# SMPSv2.net
KiCad netlist of a schematic drawn in EAGLE
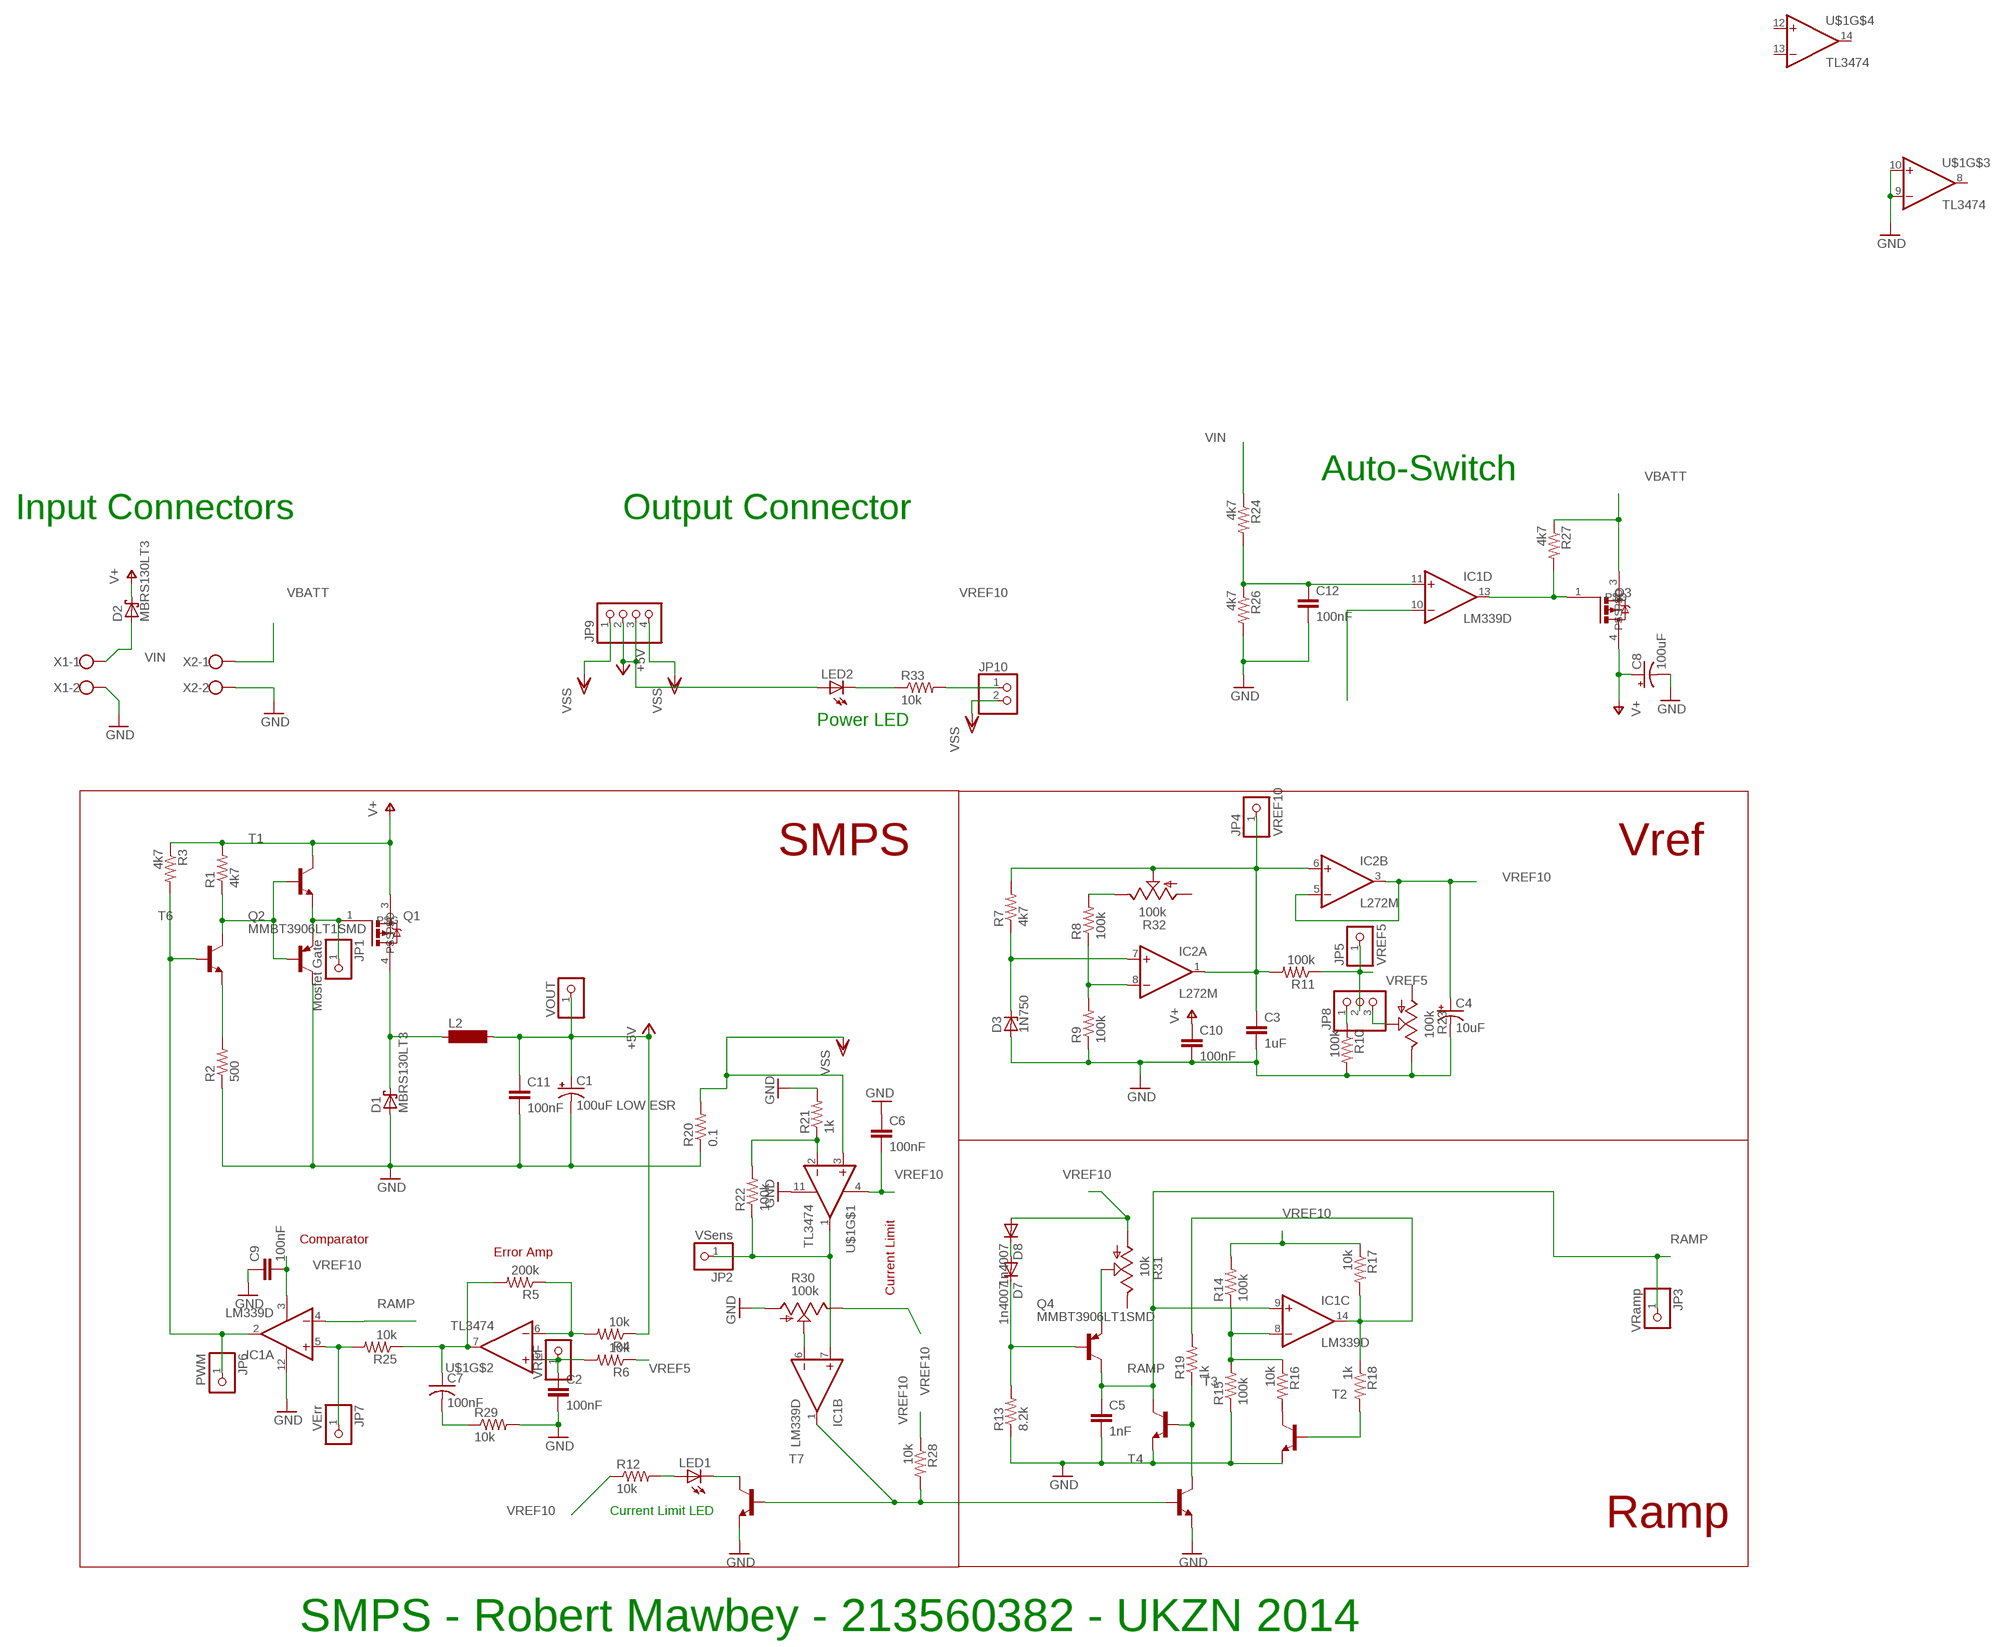
[diagram p0: schematic, sheet 1]

(export (version "E")
  (design (tool "Eeschema 10.0.6"))
  (components
    (comp (ref "C1")
      (value "100uF LOW ESR")
      (footprint "eagle-import:PANASONIC_D")
      (libsource (lib "eagle-import") (part "CPOL-USD"))
    )
    (comp (ref "C2")
      (value "100nF")
      (footprint "eagle-import:C0805")
      (libsource (lib "eagle-import") (part "C-EUC0805"))
    )
    (comp (ref "C3")
      (value "1uF")
      (footprint "eagle-import:C0805")
      (libsource (lib "eagle-import") (part "C-EUC0805"))
    )
    (comp (ref "C4")
      (value "10uF")
      (footprint "eagle-import:E5-10,5")
      (libsource (lib "eagle-import") (part "CPOL-USE5-10.5"))
    )
    (comp (ref "C5")
      (value "1nF")
      (footprint "eagle-import:C0805")
      (libsource (lib "eagle-import") (part "C-EUC0805"))
    )
    (comp (ref "C6")
      (value "100nF")
      (footprint "eagle-import:C0805")
      (libsource (lib "eagle-import") (part "C-EUC0805"))
    )
    (comp (ref "C7")
      (value "100nF")
      (footprint "eagle-import:C0805")
      (libsource (lib "eagle-import") (part "C-USC0805"))
    )
    (comp (ref "C8")
      (value "100uF")
      (footprint "eagle-import:E5-13")
      (libsource (lib "eagle-import") (part "CPOL-USE5-13"))
    )
    (comp (ref "C9")
      (value "100nF")
      (footprint "eagle-import:C0805")
      (libsource (lib "eagle-import") (part "C-EUC0805"))
    )
    (comp (ref "C10")
      (value "100nF")
      (footprint "eagle-import:C0805")
      (libsource (lib "eagle-import") (part "C-EUC0805"))
    )
    (comp (ref "C11")
      (value "100nF")
      (footprint "eagle-import:C0805")
      (libsource (lib "eagle-import") (part "C-EUC0805"))
    )
    (comp (ref "C12")
      (value "100nF")
      (footprint "eagle-import:C0805")
      (libsource (lib "eagle-import") (part "C-EUC0805"))
    )
    (comp (ref "D1")
      (value "MBRS130LT3")
      (footprint "eagle-import:SMB")
      (libsource (lib "eagle-import") (part "MBRS130LT3"))
    )
    (comp (ref "D2")
      (value "MBRS130LT3")
      (footprint "eagle-import:SMB")
      (libsource (lib "eagle-import") (part "MBRS130LT3"))
    )
    (comp (ref "D3")
      (value "1N750")
      (footprint "eagle-import:ZDIO-7.5")
      (libsource (lib "eagle-import") (part "ZENER-DIODEZD-7.5"))
    )
    (comp (ref "D7")
      (value "1n4007")
      (footprint "eagle-import:DO-214AC")
      (libsource (lib "eagle-import") (part "DIODE-DO-214AC"))
    )
    (comp (ref "D8")
      (value "1n4007")
      (footprint "eagle-import:DO-214AC")
      (libsource (lib "eagle-import") (part "DIODE-DO-214AC"))
    )
    (comp (ref "IC1")
      (value "LM339D")
      (footprint "eagle-import:SO14")
      (libsource (lib "eagle-import") (part "LM339D"))
    )
    (comp (ref "IC2")
      (value "L272M")
      (footprint "eagle-import:DIL08")
      (libsource (lib "eagle-import") (part "L272M"))
    )
    (comp (ref "JP1")
      (value "Mosfet Gate")
      (footprint "eagle-import:1X01")
      (libsource (lib "eagle-import") (part "PINHD-1X1"))
    )
    (comp (ref "JP2")
      (value "VSens")
      (footprint "eagle-import:1X01")
      (libsource (lib "eagle-import") (part "PINHD-1X1"))
    )
    (comp (ref "JP3")
      (value "VRamp")
      (footprint "eagle-import:1X01")
      (libsource (lib "eagle-import") (part "PINHD-1X1"))
    )
    (comp (ref "JP4")
      (value "VREF10")
      (footprint "eagle-import:1X01")
      (libsource (lib "eagle-import") (part "PINHD-1X1"))
    )
    (comp (ref "JP5")
      (value "VREF5")
      (footprint "eagle-import:1X01")
      (libsource (lib "eagle-import") (part "PINHD-1X1"))
    )
    (comp (ref "JP6")
      (value "PWM")
      (footprint "eagle-import:1X01")
      (libsource (lib "eagle-import") (part "PINHD-1X1"))
    )
    (comp (ref "JP7")
      (value "VErr")
      (footprint "eagle-import:1X01")
      (libsource (lib "eagle-import") (part "PINHD-1X1"))
    )
    (comp (ref "JP8")
      (value "PINHD-1X3")
      (footprint "eagle-import:1X03")
      (libsource (lib "eagle-import") (part "PINHD-1X3"))
    )
    (comp (ref "JP9")
      (value "PINHD-1X4")
      (footprint "eagle-import:1X04")
      (libsource (lib "eagle-import") (part "PINHD-1X4"))
    )
    (comp (ref "JP10")
      (value "PINHD-1X2")
      (footprint "eagle-import:1X02")
      (libsource (lib "eagle-import") (part "PINHD-1X2"))
    )
    (comp (ref "L2")
      (value "BS11")
      (footprint "eagle-import:BS11")
      (libsource (lib "eagle-import") (part "BS11"))
    )
    (comp (ref "LED1")
      (value "LEDCHIPLED_0805")
      (footprint "eagle-import:CHIPLED_0805")
      (libsource (lib "eagle-import") (part "LEDCHIPLED_0805"))
    )
    (comp (ref "LED2")
      (value "LEDCHIPLED_0805")
      (footprint "eagle-import:CHIPLED_0805")
      (libsource (lib "eagle-import") (part "LEDCHIPLED_0805"))
    )
    (comp (ref "Q1")
      (value "IRFR9024NDPAK")
      (footprint "eagle-import:D-PAK_TO252AA")
      (libsource (lib "eagle-import") (part "IRFR9024NDPAK"))
    )
    (comp (ref "Q2")
      (value "MMBT3906LT1SMD")
      (footprint "eagle-import:SOT23-BEC")
      (libsource (lib "eagle-import") (part "MMBT3906SMDLT1"))
    )
    (comp (ref "Q3")
      (value "IRFR9024NDPAK")
      (footprint "eagle-import:D-PAK_TO252AA")
      (libsource (lib "eagle-import") (part "IRFR9024NDPAK"))
    )
    (comp (ref "Q4")
      (value "MMBT3906LT1SMD")
      (footprint "eagle-import:SOT23-BEC")
      (libsource (lib "eagle-import") (part "MMBT3906SMDLT1"))
    )
    (comp (ref "R1")
      (value "4k7")
      (footprint "eagle-import:R0805")
      (libsource (lib "eagle-import") (part "R-US_R0805"))
    )
    (comp (ref "R2")
      (value "500")
      (footprint "eagle-import:R0805")
      (libsource (lib "eagle-import") (part "R-US_R0805"))
    )
    (comp (ref "R3")
      (value "4k7")
      (footprint "eagle-import:R0805")
      (libsource (lib "eagle-import") (part "R-US_R0805"))
    )
    (comp (ref "R4")
      (value "10k")
      (footprint "eagle-import:R0805")
      (libsource (lib "eagle-import") (part "R-US_R0805"))
    )
    (comp (ref "R5")
      (value "200k")
      (footprint "eagle-import:R0805")
      (libsource (lib "eagle-import") (part "R-US_R0805"))
    )
    (comp (ref "R6")
      (value "10k")
      (footprint "eagle-import:R0805")
      (libsource (lib "eagle-import") (part "R-US_R0805"))
    )
    (comp (ref "R7")
      (value "4k7")
      (footprint "eagle-import:R0805")
      (libsource (lib "eagle-import") (part "R-US_R0805"))
    )
    (comp (ref "R8")
      (value "100k")
      (footprint "eagle-import:R0805")
      (libsource (lib "eagle-import") (part "R-US_R0805"))
    )
    (comp (ref "R9")
      (value "100k")
      (footprint "eagle-import:R0805")
      (libsource (lib "eagle-import") (part "R-US_R0805"))
    )
    (comp (ref "R10")
      (value "100k")
      (footprint "eagle-import:R0805")
      (libsource (lib "eagle-import") (part "R-US_R0805"))
    )
    (comp (ref "R11")
      (value "100k")
      (footprint "eagle-import:R0805")
      (libsource (lib "eagle-import") (part "R-US_R0805"))
    )
    (comp (ref "R12")
      (value "10k")
      (footprint "eagle-import:R0805")
      (libsource (lib "eagle-import") (part "R-US_R0805"))
    )
    (comp (ref "R13")
      (value "8.2k")
      (footprint "eagle-import:R0805")
      (libsource (lib "eagle-import") (part "R-US_R0805"))
    )
    (comp (ref "R14")
      (value "100k")
      (footprint "eagle-import:R0805")
      (libsource (lib "eagle-import") (part "R-US_R0805"))
    )
    (comp (ref "R15")
      (value "100k")
      (footprint "eagle-import:R0805")
      (libsource (lib "eagle-import") (part "R-US_R0805"))
    )
    (comp (ref "R16")
      (value "10k")
      (footprint "eagle-import:R0805")
      (libsource (lib "eagle-import") (part "R-US_R0805"))
    )
    (comp (ref "R17")
      (value "10k")
      (footprint "eagle-import:R0805")
      (libsource (lib "eagle-import") (part "R-US_R0805"))
    )
    (comp (ref "R18")
      (value "1k")
      (footprint "eagle-import:R0805")
      (libsource (lib "eagle-import") (part "R-US_R0805"))
    )
    (comp (ref "R19")
      (value "1k")
      (footprint "eagle-import:R0805")
      (libsource (lib "eagle-import") (part "R-US_R0805"))
    )
    (comp (ref "R20")
      (value "0.1")
      (footprint "eagle-import:R1206")
      (libsource (lib "eagle-import") (part "R-US_R1206"))
    )
    (comp (ref "R21")
      (value "1k")
      (footprint "eagle-import:R0805")
      (libsource (lib "eagle-import") (part "R-US_R0805"))
    )
    (comp (ref "R22")
      (value "100k")
      (footprint "eagle-import:R0805")
      (libsource (lib "eagle-import") (part "R-US_R0805"))
    )
    (comp (ref "R23")
      (value "100k")
      (footprint "eagle-import:B25P")
      (libsource (lib "eagle-import") (part "TRIM_US-B25P"))
    )
    (comp (ref "R24")
      (value "4k7")
      (footprint "eagle-import:R0805")
      (libsource (lib "eagle-import") (part "R-US_R0805"))
    )
    (comp (ref "R25")
      (value "10k")
      (footprint "eagle-import:R0805")
      (libsource (lib "eagle-import") (part "R-US_R0805"))
    )
    (comp (ref "R26")
      (value "4k7")
      (footprint "eagle-import:R0805")
      (libsource (lib "eagle-import") (part "R-US_R0805"))
    )
    (comp (ref "R27")
      (value "4k7")
      (footprint "eagle-import:R0805")
      (libsource (lib "eagle-import") (part "R-US_R0805"))
    )
    (comp (ref "R28")
      (value "10k")
      (footprint "eagle-import:R0805")
      (libsource (lib "eagle-import") (part "R-US_R0805"))
    )
    (comp (ref "R29")
      (value "10k")
      (footprint "eagle-import:R0805")
      (libsource (lib "eagle-import") (part "R-US_R0805"))
    )
    (comp (ref "R30")
      (value "100k")
      (footprint "eagle-import:B25P")
      (libsource (lib "eagle-import") (part "TRIM_US-B25P"))
    )
    (comp (ref "R31")
      (value "10k")
      (footprint "eagle-import:B25P")
      (libsource (lib "eagle-import") (part "TRIM_US-B25P"))
    )
    (comp (ref "R32")
      (value "100k")
      (footprint "eagle-import:B25P")
      (libsource (lib "eagle-import") (part "TRIM_US-B25P"))
    )
    (comp (ref "R33")
      (value "10k")
      (footprint "eagle-import:R0805")
      (libsource (lib "eagle-import") (part "R-US_R0805"))
    )
    (comp (ref "T1")
      (value "MMBT2222ALT1-NPN-SOT23-BEC")
      (footprint "eagle-import:SOT23-BEC")
      (libsource (lib "eagle-import") (part "-NPN-SOT23-BECMMBT2222ALT1"))
    )
    (comp (ref "T2")
      (value "MMBT2222ALT1-NPN-SOT23-BEC")
      (footprint "eagle-import:SOT23-BEC")
      (libsource (lib "eagle-import") (part "-NPN-SOT23-BECMMBT2222ALT1"))
    )
    (comp (ref "T3")
      (value "MMBT2222ALT1-NPN-SOT23-BEC")
      (footprint "eagle-import:SOT23-BEC")
      (libsource (lib "eagle-import") (part "-NPN-SOT23-BECMMBT2222ALT1"))
    )
    (comp (ref "T4")
      (value "MMBT2222ALT1-NPN-SOT23-BEC")
      (footprint "eagle-import:SOT23-BEC")
      (libsource (lib "eagle-import") (part "-NPN-SOT23-BECMMBT2222ALT1"))
    )
    (comp (ref "T6")
      (value "MMBT2222ALT1-NPN-SOT23-BEC")
      (footprint "eagle-import:SOT23-BEC")
      (libsource (lib "eagle-import") (part "-NPN-SOT23-BECMMBT2222ALT1"))
    )
    (comp (ref "T7")
      (value "MMBT2222ALT1-NPN-SOT23-BEC")
      (footprint "eagle-import:SOT23-BEC")
      (libsource (lib "eagle-import") (part "-NPN-SOT23-BECMMBT2222ALT1"))
    )
    (comp (ref "U$1")
      (value "TL3474")
      (footprint "eagle-import:SO14")
      (libsource (lib "eagle-import") (part "TL3474"))
    )
    (comp (ref "VOUT")
      (value "PINHD-1X1")
      (footprint "eagle-import:1X01")
      (libsource (lib "eagle-import") (part "PINHD-1X1"))
    )
    (comp (ref "VREF")
      (value "PINHD-1X1")
      (footprint "eagle-import:1X01")
      (libsource (lib "eagle-import") (part "PINHD-1X1"))
    )
    (comp (ref "X1")
      (value "W237-102")
      (footprint "eagle-import:W237-102")
      (fields (field (name "MPN") "237-102"))
      (libsource (lib "eagle-import") (part "W237-102"))
    )
    (comp (ref "X2")
      (value "W237-102")
      (footprint "eagle-import:W237-102")
      (fields
        (field (name "MPN") "237-102")
        (field (name "MPN_1") "237-102")
        (field (name "OC_FARNELL") "unknown")
        (field (name "OC_NEWARK") "70K9898")
      )
      (libsource (lib "eagle-import") (part "W237-102"))
    )
  )
  (nets
    (net (code "1") (name "+5V") (class "Default")
      (node (ref "C1") (pin "+") (pinfunction "+_+") (pintype "passive"))
      (node (ref "C11") (pin "1") (pinfunction "1_1") (pintype "passive"))
      (node (ref "JP9") (pin "2") (pinfunction "2_2") (pintype "passive"))
      (node (ref "JP9") (pin "3") (pinfunction "3_3") (pintype "passive"))
      (node (ref "L2") (pin "2") (pinfunction "2_2") (pintype "passive"))
      (node (ref "LED2") (pin "A") (pinfunction "A_A") (pintype "passive"))
      (node (ref "R4") (pin "1") (pinfunction "1_1") (pintype "passive"))
      (node (ref "VOUT") (pin "1") (pinfunction "1_1") (pintype "passive"))
    )
    (net (code "2") (name "/RAMP") (class "Default")
      (node (ref "C5") (pin "1") (pinfunction "1_1") (pintype "passive"))
      (node (ref "IC1") (pin "4") (pinfunction "-IN_4") (pintype "input"))
      (node (ref "IC1") (pin "9") (pinfunction "+IN_9") (pintype "input"))
      (node (ref "JP3") (pin "1") (pinfunction "1_1") (pintype "passive"))
      (node (ref "Q4") (pin "C") (pinfunction "C_C") (pintype "passive"))
      (node (ref "T3") (pin "C") (pinfunction "C_C") (pintype "passive"))
    )
    (net (code "3") (name "/VBATT") (class "Default")
      (node (ref "Q3") (pin "3") (pinfunction "P$S_3") (pintype "bidirectional"))
      (node (ref "R27") (pin "1") (pinfunction "1_1") (pintype "passive"))
      (node (ref "X2") (pin "1") (pinfunction "KL_1") (pintype "passive"))
    )
    (net (code "4") (name "/VIN") (class "Default")
      (node (ref "D2") (pin "A") (pinfunction "A_A") (pintype "passive"))
      (node (ref "R24") (pin "1") (pinfunction "1_1") (pintype "passive"))
      (node (ref "X1") (pin "1") (pinfunction "KL_1") (pintype "passive"))
    )
    (net (code "5") (name "/VREF5") (class "Default")
      (node (ref "JP5") (pin "1") (pinfunction "1_1") (pintype "passive"))
      (node (ref "JP8") (pin "2") (pinfunction "2_2") (pintype "passive"))
      (node (ref "R11") (pin "1") (pinfunction "1_1") (pintype "passive"))
      (node (ref "R6") (pin "1") (pinfunction "1_1") (pintype "passive"))
    )
    (net (code "6") (name "/VREF10") (class "Default")
      (node (ref "C4") (pin "+") (pinfunction "+_+") (pintype "passive"))
      (node (ref "C6") (pin "2") (pinfunction "2_2") (pintype "passive"))
      (node (ref "C9") (pin "2") (pinfunction "2_2") (pintype "passive"))
      (node (ref "D8") (pin "A") (pinfunction "A_A") (pintype "passive"))
      (node (ref "IC1") (pin "10") (pinfunction "-IN_10") (pintype "input"))
      (node (ref "IC1") (pin "3") (pinfunction "V+_3") (pintype "power_in"))
      (node (ref "IC2") (pin "3") (pinfunction "OUT_3") (pintype "output"))
      (node (ref "IC2") (pin "5") (pinfunction "-IN_5") (pintype "input"))
      (node (ref "R12") (pin "1") (pinfunction "1_1") (pintype "passive"))
      (node (ref "R14") (pin "2") (pinfunction "2_2") (pintype "passive"))
      (node (ref "R17") (pin "1") (pinfunction "1_1") (pintype "passive"))
      (node (ref "R28") (pin "1") (pinfunction "1_1") (pintype "passive"))
      (node (ref "R30") (pin "E") (pinfunction "E_E") (pintype "passive"))
      (node (ref "R31") (pin "A") (pinfunction "A_A") (pintype "passive"))
      (node (ref "U$1") (pin "4") (pinfunction "V+_4") (pintype "power_in"))
    )
    (net (code "7") (name "GND") (class "Default")
      (node (ref "C1") (pin "-") (pinfunction "-_-") (pintype "passive"))
      (node (ref "C10") (pin "2") (pinfunction "2_2") (pintype "passive"))
      (node (ref "C11") (pin "2") (pinfunction "2_2") (pintype "passive"))
      (node (ref "C12") (pin "2") (pinfunction "2_2") (pintype "passive"))
      (node (ref "C2") (pin "2") (pinfunction "2_2") (pintype "passive"))
      (node (ref "C3") (pin "2") (pinfunction "2_2") (pintype "passive"))
      (node (ref "C4") (pin "-") (pinfunction "-_-") (pintype "passive"))
      (node (ref "C5") (pin "2") (pinfunction "2_2") (pintype "passive"))
      (node (ref "C6") (pin "1") (pinfunction "1_1") (pintype "passive"))
      (node (ref "C8") (pin "-") (pinfunction "-_-") (pintype "passive"))
      (node (ref "C9") (pin "1") (pinfunction "1_1") (pintype "passive"))
      (node (ref "D1") (pin "A") (pinfunction "A_A") (pintype "passive"))
      (node (ref "D3") (pin "A") (pinfunction "A_A") (pintype "passive"))
      (node (ref "IC1") (pin "12") (pinfunction "GND_12") (pintype "power_in"))
      (node (ref "Q2") (pin "C") (pinfunction "C_C") (pintype "passive"))
      (node (ref "R10") (pin "2") (pinfunction "2_2") (pintype "passive"))
      (node (ref "R13") (pin "1") (pinfunction "1_1") (pintype "passive"))
      (node (ref "R15") (pin "1") (pinfunction "1_1") (pintype "passive"))
      (node (ref "R2") (pin "1") (pinfunction "1_1") (pintype "passive"))
      (node (ref "R20") (pin "1") (pinfunction "1_1") (pintype "passive"))
      (node (ref "R21") (pin "2") (pinfunction "2_2") (pintype "passive"))
      (node (ref "R23") (pin "E") (pinfunction "E_E") (pintype "passive"))
      (node (ref "R26") (pin "2") (pinfunction "2_2") (pintype "passive"))
      (node (ref "R29") (pin "2") (pinfunction "2_2") (pintype "passive"))
      (node (ref "R30") (pin "A") (pinfunction "A_A") (pintype "passive"))
      (node (ref "R9") (pin "1") (pinfunction "1_1") (pintype "passive"))
      (node (ref "T2") (pin "E") (pinfunction "E_E") (pintype "passive"))
      (node (ref "T3") (pin "E") (pinfunction "E_E") (pintype "passive"))
      (node (ref "T4") (pin "E") (pinfunction "E_E") (pintype "passive"))
      (node (ref "T7") (pin "E") (pinfunction "E_E") (pintype "passive"))
      (node (ref "U$1") (pin "10") (pinfunction "+IN_10") (pintype "input"))
      (node (ref "U$1") (pin "11") (pinfunction "V-_11") (pintype "power_in"))
      (node (ref "U$1") (pin "9") (pinfunction "-IN_9") (pintype "input"))
      (node (ref "X1") (pin "2") (pinfunction "KL_2") (pintype "passive"))
      (node (ref "X2") (pin "2") (pinfunction "KL_2") (pintype "passive"))
    )
    (net (code "8") (name "Net-(C7-Pad2)") (class "Default")
      (node (ref "C7") (pin "2") (pinfunction "2_2") (pintype "passive"))
      (node (ref "R29") (pin "1") (pinfunction "1_1") (pintype "passive"))
    )
    (net (code "9") (name "Net-(D7-PadA)") (class "Default")
      (node (ref "D7") (pin "A") (pinfunction "A_A") (pintype "passive"))
      (node (ref "D8") (pin "C") (pinfunction "C_C") (pintype "passive"))
    )
    (net (code "10") (name "Net-(D7-PadC)") (class "Default")
      (node (ref "D7") (pin "C") (pinfunction "C_C") (pintype "passive"))
      (node (ref "Q4") (pin "B") (pinfunction "B_B") (pintype "passive"))
      (node (ref "R13") (pin "2") (pinfunction "2_2") (pintype "passive"))
    )
    (net (code "11") (name "Net-(IC1A-+IN)") (class "Default")
      (node (ref "IC1") (pin "5") (pinfunction "+IN_5") (pintype "input"))
      (node (ref "JP7") (pin "1") (pinfunction "1_1") (pintype "passive"))
      (node (ref "R25") (pin "2") (pinfunction "2_2") (pintype "passive"))
    )
    (net (code "12") (name "Net-(IC1A-OUT)") (class "Default")
      (node (ref "IC1") (pin "2") (pinfunction "OUT_2") (pintype "open_collector"))
      (node (ref "JP6") (pin "1") (pinfunction "1_1") (pintype "passive"))
      (node (ref "R3") (pin "2") (pinfunction "2_2") (pintype "passive"))
      (node (ref "T6") (pin "B") (pinfunction "B_B") (pintype "passive"))
    )
    (net (code "13") (name "Net-(IC1B-+IN)") (class "Default")
      (node (ref "IC1") (pin "7") (pinfunction "+IN_7") (pintype "input"))
      (node (ref "JP2") (pin "1") (pinfunction "1_1") (pintype "passive"))
      (node (ref "R22") (pin "1") (pinfunction "1_1") (pintype "passive"))
      (node (ref "U$1") (pin "1") (pinfunction "OUT_1") (pintype "output"))
    )
    (net (code "14") (name "Net-(IC1B--IN)") (class "Default")
      (node (ref "IC1") (pin "6") (pinfunction "-IN_6") (pintype "input"))
      (node (ref "R30") (pin "S") (pinfunction "S_S") (pintype "passive"))
    )
    (net (code "15") (name "Net-(IC1B-OUT)") (class "Default")
      (node (ref "IC1") (pin "1") (pinfunction "OUT_1") (pintype "open_collector"))
      (node (ref "R28") (pin "2") (pinfunction "2_2") (pintype "passive"))
      (node (ref "T4") (pin "B") (pinfunction "B_B") (pintype "passive"))
      (node (ref "T7") (pin "B") (pinfunction "B_B") (pintype "passive"))
    )
    (net (code "16") (name "Net-(IC1C--IN)") (class "Default")
      (node (ref "IC1") (pin "8") (pinfunction "-IN_8") (pintype "input"))
      (node (ref "R14") (pin "1") (pinfunction "1_1") (pintype "passive"))
      (node (ref "R15") (pin "2") (pinfunction "2_2") (pintype "passive"))
      (node (ref "R16") (pin "1") (pinfunction "1_1") (pintype "passive"))
    )
    (net (code "17") (name "Net-(IC1C-OUT)") (class "Default")
      (node (ref "IC1") (pin "14") (pinfunction "OUT_14") (pintype "open_collector"))
      (node (ref "R17") (pin "2") (pinfunction "2_2") (pintype "passive"))
      (node (ref "R18") (pin "1") (pinfunction "1_1") (pintype "passive"))
      (node (ref "R19") (pin "2") (pinfunction "2_2") (pintype "passive"))
    )
    (net (code "18") (name "Net-(IC1D-+IN)") (class "Default")
      (node (ref "C12") (pin "1") (pinfunction "1_1") (pintype "passive"))
      (node (ref "IC1") (pin "11") (pinfunction "+IN_11") (pintype "input"))
      (node (ref "R24") (pin "2") (pinfunction "2_2") (pintype "passive"))
      (node (ref "R26") (pin "1") (pinfunction "1_1") (pintype "passive"))
    )
    (net (code "19") (name "Net-(IC1D-OUT)") (class "Default")
      (node (ref "IC1") (pin "13") (pinfunction "OUT_13") (pintype "open_collector"))
      (node (ref "Q3") (pin "1") (pinfunction "P$G_1") (pintype "bidirectional"))
      (node (ref "R27") (pin "2") (pinfunction "2_2") (pintype "passive"))
    )
    (net (code "20") (name "Net-(IC2A-+IN)") (class "Default")
      (node (ref "D3") (pin "C") (pinfunction "C_C") (pintype "passive"))
      (node (ref "IC2") (pin "7") (pinfunction "+IN_7") (pintype "input"))
      (node (ref "R7") (pin "1") (pinfunction "1_1") (pintype "passive"))
    )
    (net (code "21") (name "Net-(IC2A--IN)") (class "Default")
      (node (ref "IC2") (pin "8") (pinfunction "-IN_8") (pintype "input"))
      (node (ref "R8") (pin "1") (pinfunction "1_1") (pintype "passive"))
      (node (ref "R9") (pin "2") (pinfunction "2_2") (pintype "passive"))
    )
    (net (code "22") (name "Net-(IC2A-OUT)") (class "Default")
      (node (ref "C3") (pin "1") (pinfunction "1_1") (pintype "passive"))
      (node (ref "IC2") (pin "1") (pinfunction "OUT_1") (pintype "output"))
      (node (ref "IC2") (pin "6") (pinfunction "+IN_6") (pintype "input"))
      (node (ref "JP4") (pin "1") (pinfunction "1_1") (pintype "passive"))
      (node (ref "R11") (pin "2") (pinfunction "2_2") (pintype "passive"))
      (node (ref "R32") (pin "S") (pinfunction "S_S") (pintype "passive"))
      (node (ref "R7") (pin "2") (pinfunction "2_2") (pintype "passive"))
    )
    (net (code "23") (name "Net-(JP8-Pad1)") (class "Default")
      (node (ref "JP8") (pin "1") (pinfunction "1_1") (pintype "passive"))
      (node (ref "R10") (pin "1") (pinfunction "1_1") (pintype "passive"))
    )
    (net (code "24") (name "Net-(JP8-Pad3)") (class "Default")
      (node (ref "JP8") (pin "3") (pinfunction "3_3") (pintype "passive"))
      (node (ref "R23") (pin "S") (pinfunction "S_S") (pintype "passive"))
    )
    (net (code "25") (name "Net-(JP10-Pad1)") (class "Default")
      (node (ref "JP10") (pin "1") (pinfunction "1_1") (pintype "passive"))
      (node (ref "R33") (pin "2") (pinfunction "2_2") (pintype "passive"))
    )
    (net (code "26") (name "Net-(LED1-PadA)") (class "Default")
      (node (ref "LED1") (pin "A") (pinfunction "A_A") (pintype "passive"))
      (node (ref "R12") (pin "2") (pinfunction "2_2") (pintype "passive"))
    )
    (net (code "27") (name "Net-(LED1-PadC)") (class "Default")
      (node (ref "LED1") (pin "C") (pinfunction "C_C") (pintype "passive"))
      (node (ref "T7") (pin "C") (pinfunction "C_C") (pintype "passive"))
    )
    (net (code "28") (name "Net-(LED2-PadC)") (class "Default")
      (node (ref "LED2") (pin "C") (pinfunction "C_C") (pintype "passive"))
      (node (ref "R33") (pin "1") (pinfunction "1_1") (pintype "passive"))
    )
    (net (code "29") (name "Net-(Q1-P$D)") (class "Default")
      (node (ref "D1") (pin "C") (pinfunction "C_C") (pintype "passive"))
      (node (ref "L2") (pin "1") (pinfunction "1_1") (pintype "passive"))
      (node (ref "Q1") (pin "4") (pinfunction "P$D_4") (pintype "bidirectional"))
    )
    (net (code "30") (name "Net-(Q1-P$G)") (class "Default")
      (node (ref "JP1") (pin "1") (pinfunction "1_1") (pintype "passive"))
      (node (ref "Q1") (pin "1") (pinfunction "P$G_1") (pintype "bidirectional"))
      (node (ref "Q2") (pin "E") (pinfunction "E_E") (pintype "passive"))
      (node (ref "T1") (pin "E") (pinfunction "E_E") (pintype "passive"))
    )
    (net (code "31") (name "Net-(Q2-PadB)") (class "Default")
      (node (ref "Q2") (pin "B") (pinfunction "B_B") (pintype "passive"))
      (node (ref "R1") (pin "1") (pinfunction "1_1") (pintype "passive"))
      (node (ref "T1") (pin "B") (pinfunction "B_B") (pintype "passive"))
      (node (ref "T6") (pin "C") (pinfunction "C_C") (pintype "passive"))
    )
    (net (code "32") (name "Net-(Q4-PadE)") (class "Default")
      (node (ref "Q4") (pin "E") (pinfunction "E_E") (pintype "passive"))
      (node (ref "R31") (pin "S") (pinfunction "S_S") (pintype "passive"))
    )
    (net (code "33") (name "Net-(R2-Pad2)") (class "Default")
      (node (ref "R2") (pin "2") (pinfunction "2_2") (pintype "passive"))
      (node (ref "T6") (pin "E") (pinfunction "E_E") (pintype "passive"))
    )
    (net (code "34") (name "Net-(R16-Pad2)") (class "Default")
      (node (ref "R16") (pin "2") (pinfunction "2_2") (pintype "passive"))
      (node (ref "T2") (pin "C") (pinfunction "C_C") (pintype "passive"))
    )
    (net (code "35") (name "Net-(R18-Pad2)") (class "Default")
      (node (ref "R18") (pin "2") (pinfunction "2_2") (pintype "passive"))
      (node (ref "T2") (pin "B") (pinfunction "B_B") (pintype "passive"))
    )
    (net (code "36") (name "Net-(R19-Pad1)") (class "Default")
      (node (ref "R19") (pin "1") (pinfunction "1_1") (pintype "passive"))
      (node (ref "T3") (pin "B") (pinfunction "B_B") (pintype "passive"))
      (node (ref "T4") (pin "C") (pinfunction "C_C") (pintype "passive"))
    )
    (net (code "37") (name "Net-(R32-PadE)") (class "Default")
      (node (ref "R32") (pin "E") (pinfunction "E_E") (pintype "passive"))
      (node (ref "R8") (pin "2") (pinfunction "2_2") (pintype "passive"))
    )
    (net (code "38") (name "Net-(U$1A--IN)") (class "Default")
      (node (ref "R21") (pin "1") (pinfunction "1_1") (pintype "passive"))
      (node (ref "R22") (pin "2") (pinfunction "2_2") (pintype "passive"))
      (node (ref "U$1") (pin "2") (pinfunction "-IN_2") (pintype "input"))
    )
    (net (code "39") (name "Net-(U$1B-+IN)") (class "Default")
      (node (ref "C2") (pin "1") (pinfunction "1_1") (pintype "passive"))
      (node (ref "R6") (pin "2") (pinfunction "2_2") (pintype "passive"))
      (node (ref "U$1") (pin "5") (pinfunction "+IN_5") (pintype "input"))
      (node (ref "VREF") (pin "1") (pinfunction "1_1") (pintype "passive"))
    )
    (net (code "40") (name "Net-(U$1B--IN)") (class "Default")
      (node (ref "R4") (pin "2") (pinfunction "2_2") (pintype "passive"))
      (node (ref "R5") (pin "1") (pinfunction "1_1") (pintype "passive"))
      (node (ref "U$1") (pin "6") (pinfunction "-IN_6") (pintype "input"))
    )
    (net (code "41") (name "Net-(U$1B-OUT)") (class "Default")
      (node (ref "C7") (pin "1") (pinfunction "1_1") (pintype "passive"))
      (node (ref "R25") (pin "1") (pinfunction "1_1") (pintype "passive"))
      (node (ref "R5") (pin "2") (pinfunction "2_2") (pintype "passive"))
      (node (ref "U$1") (pin "7") (pinfunction "OUT_7") (pintype "output"))
    )
    (net (code "42") (name "V+") (class "Default")
      (node (ref "C10") (pin "1") (pinfunction "1_1") (pintype "passive"))
      (node (ref "C8") (pin "+") (pinfunction "+_+") (pintype "passive"))
      (node (ref "D2") (pin "C") (pinfunction "C_C") (pintype "passive"))
      (node (ref "Q1") (pin "3") (pinfunction "P$S_3") (pintype "bidirectional"))
      (node (ref "Q3") (pin "4") (pinfunction "P$D_4") (pintype "bidirectional"))
      (node (ref "R1") (pin "2") (pinfunction "2_2") (pintype "passive"))
      (node (ref "R3") (pin "1") (pinfunction "1_1") (pintype "passive"))
      (node (ref "T1") (pin "C") (pinfunction "C_C") (pintype "passive"))
    )
    (net (code "43") (name "VSS") (class "Default")
      (node (ref "JP10") (pin "2") (pinfunction "2_2") (pintype "passive"))
      (node (ref "JP9") (pin "1") (pinfunction "1_1") (pintype "passive"))
      (node (ref "JP9") (pin "4") (pinfunction "4_4") (pintype "passive"))
      (node (ref "R20") (pin "2") (pinfunction "2_2") (pintype "passive"))
      (node (ref "U$1") (pin "3") (pinfunction "+IN_3") (pintype "input"))
    )
    (net (code "44") (name "unconnected-(R23-PadA)") (class "Default")
      (node (ref "R23") (pin "A") (pinfunction "A_A") (pintype "passive"))
    )
    (net (code "45") (name "unconnected-(R31-PadE)") (class "Default")
      (node (ref "R31") (pin "E") (pinfunction "E_E") (pintype "passive"))
    )
    (net (code "46") (name "unconnected-(R32-PadA)") (class "Default")
      (node (ref "R32") (pin "A") (pinfunction "A_A") (pintype "passive"))
    )
    (net (code "47") (name "unconnected-(U$1C-OUT-Pad8)") (class "Default")
      (node (ref "U$1") (pin "8") (pinfunction "OUT_8") (pintype "output"))
    )
    (net (code "48") (name "unconnected-(U$1D-+IN-Pad12)") (class "Default")
      (node (ref "U$1") (pin "12") (pinfunction "+IN_12") (pintype "input"))
    )
    (net (code "49") (name "unconnected-(U$1D--IN-Pad13)") (class "Default")
      (node (ref "U$1") (pin "13") (pinfunction "-IN_13") (pintype "input"))
    )
    (net (code "50") (name "unconnected-(U$1D-OUT-Pad14)") (class "Default")
      (node (ref "U$1") (pin "14") (pinfunction "OUT_14") (pintype "output"))
    )
  )
)
